# Cab_Board.net
KiCad netlist of a schematic drawn in EAGLE
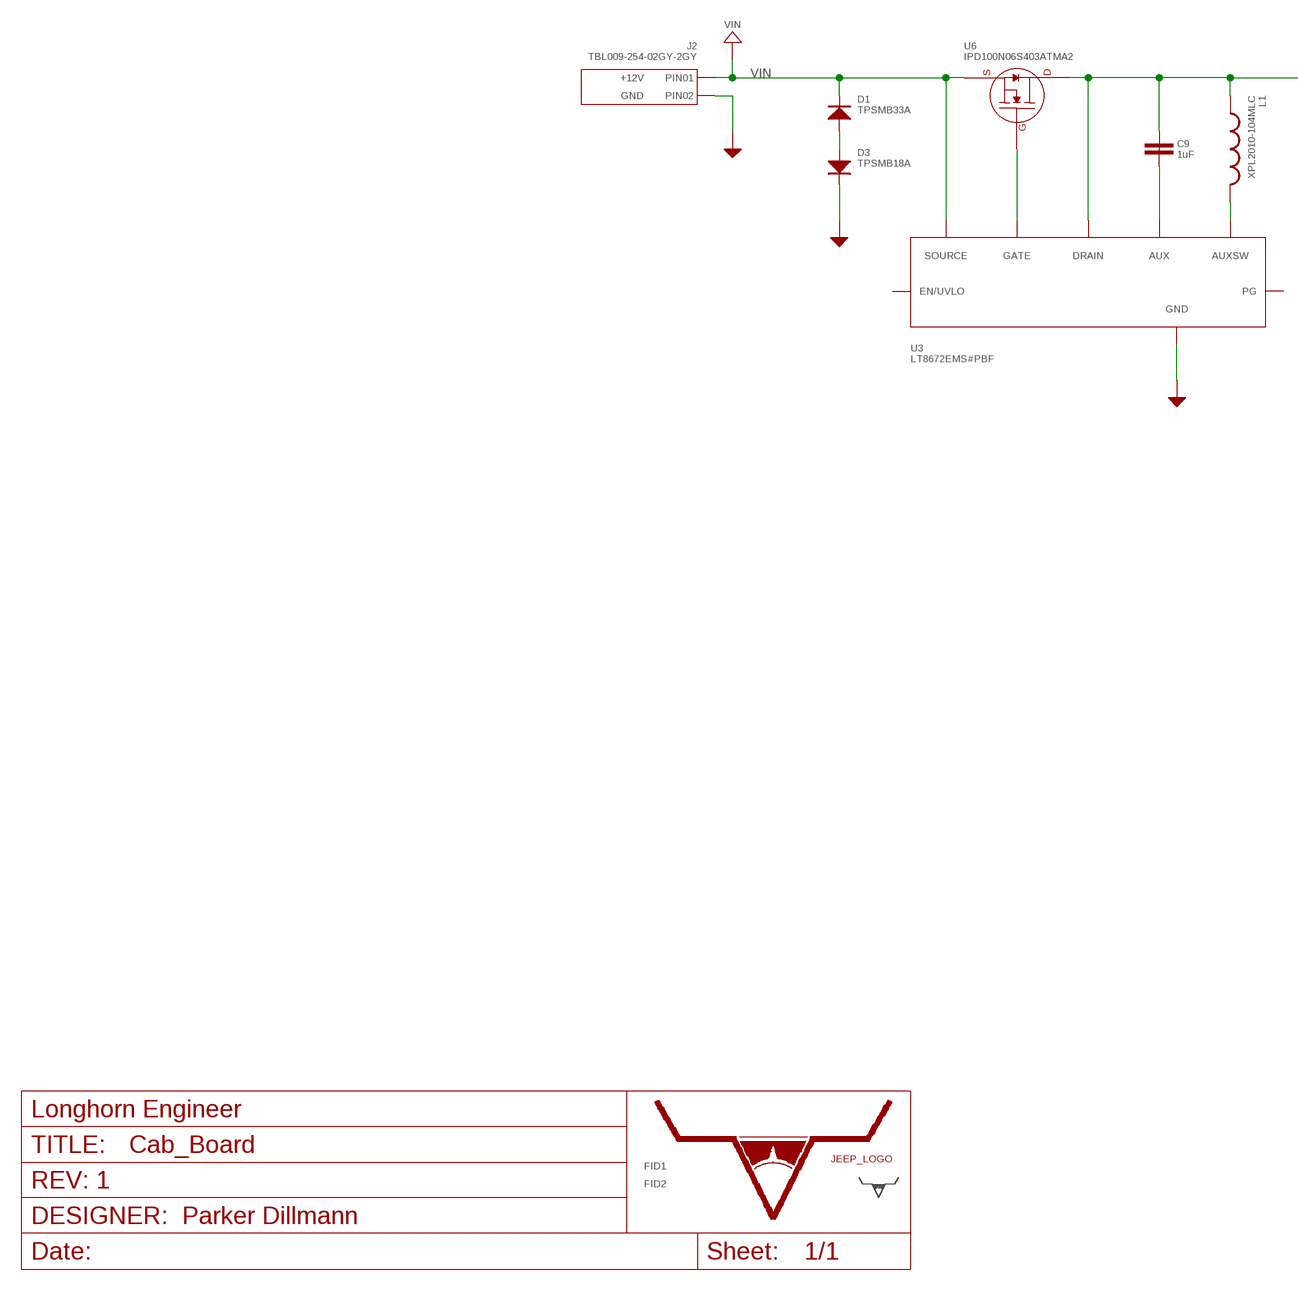
[diagram p0: schematic, sheet 1, part 1 of 3]
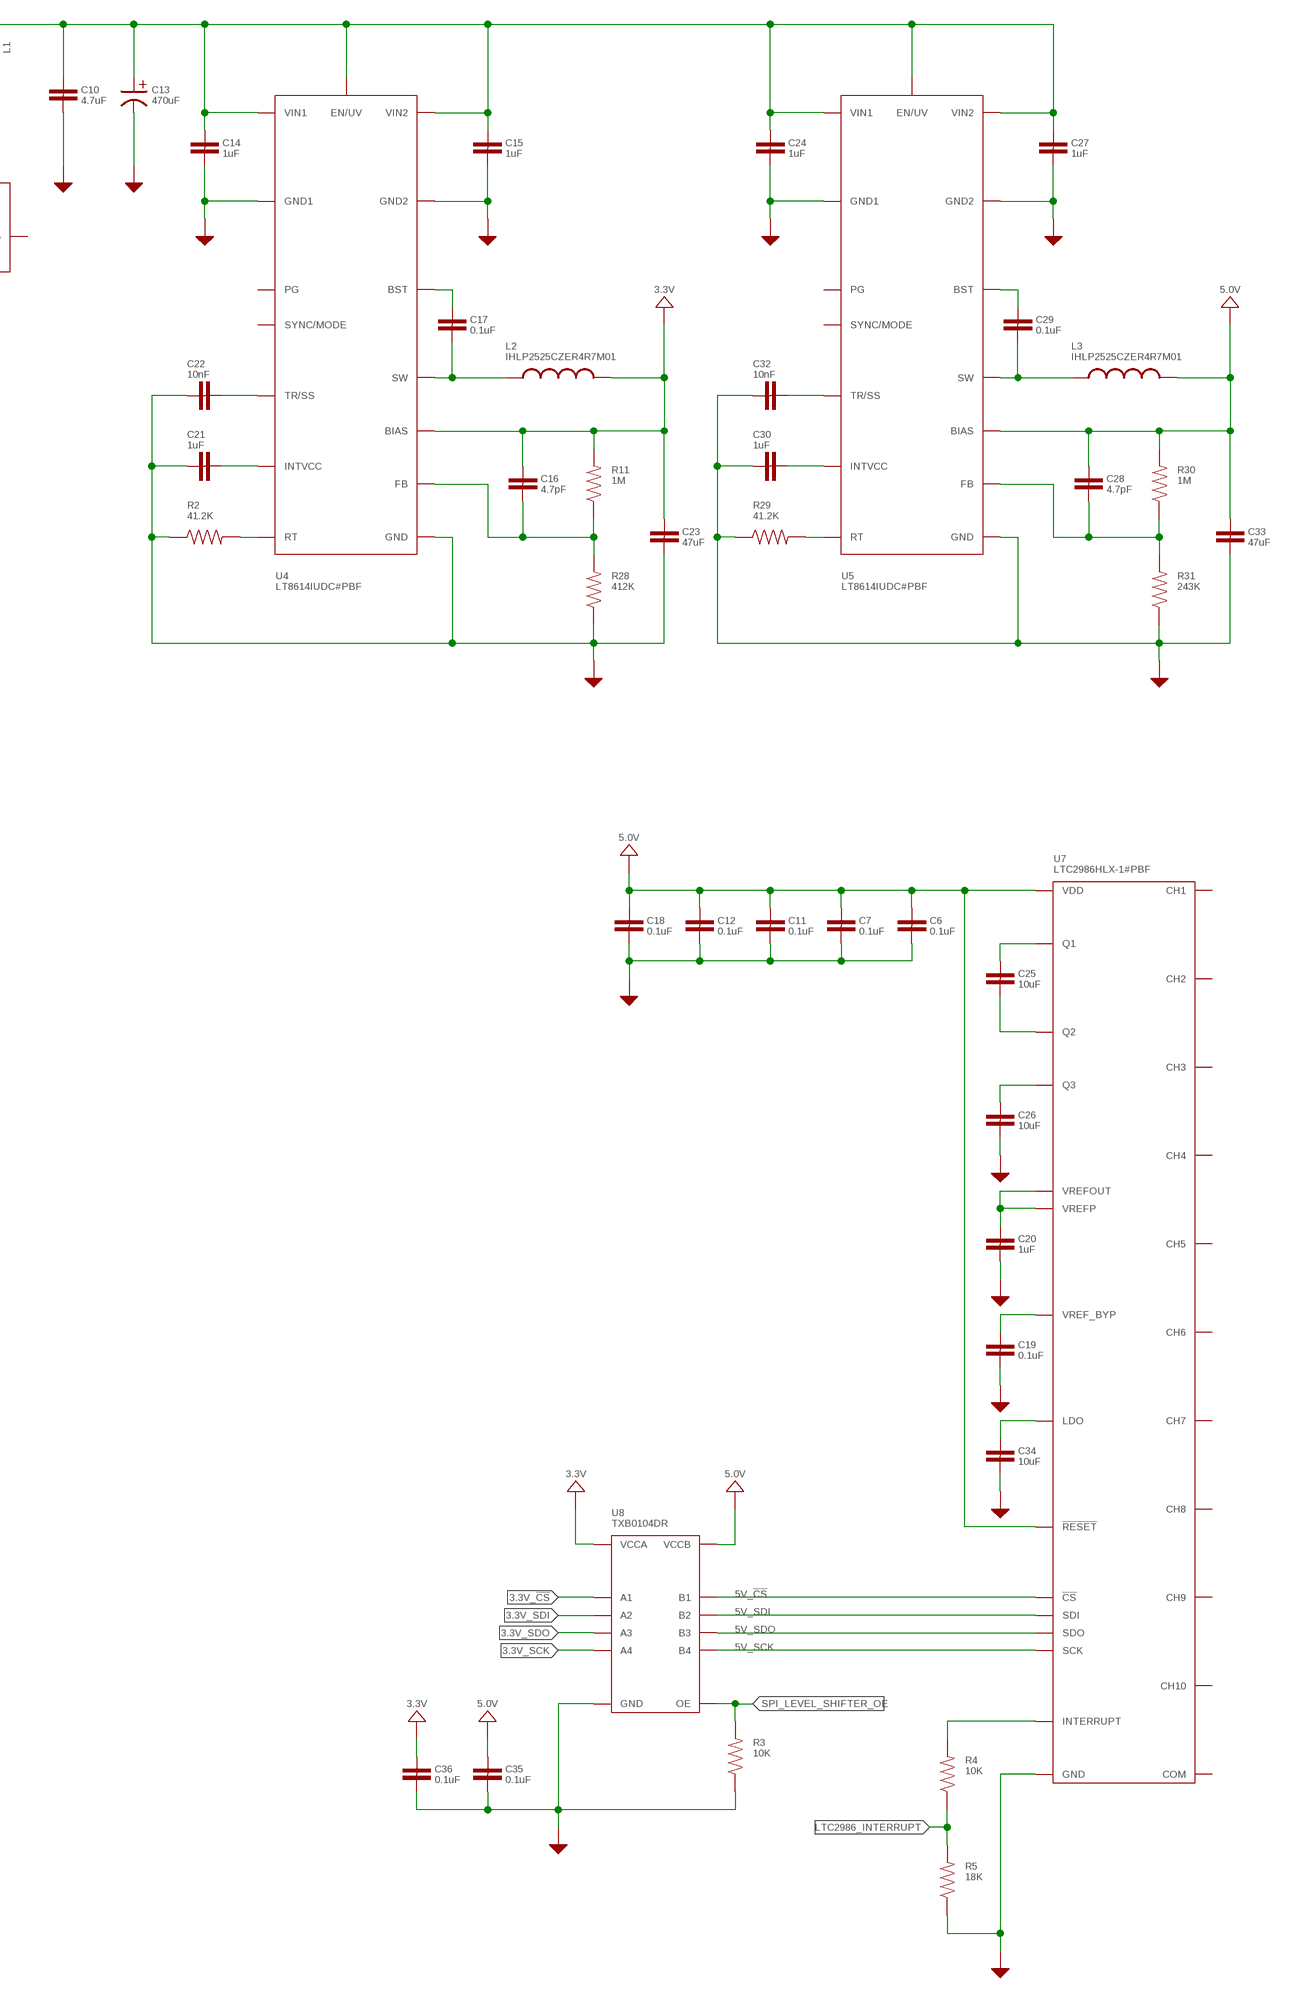
[diagram p1: schematic, sheet 1, part 2 of 3]
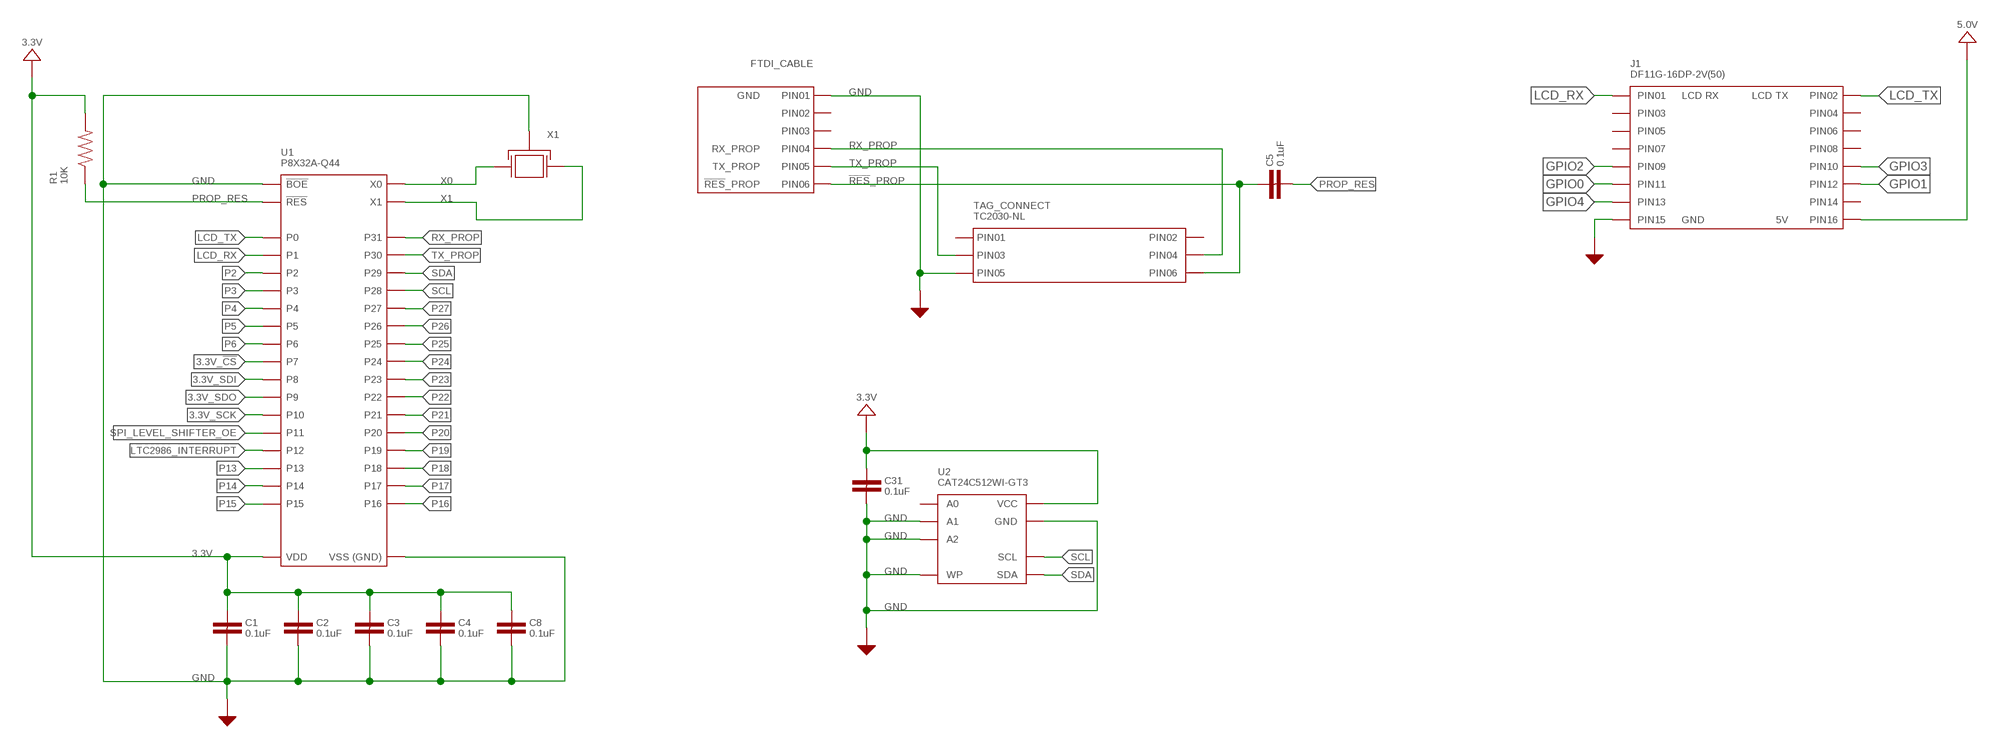
[diagram p2: schematic, sheet 1, part 3 of 3]

(export (version "E")
  (design (tool "Eeschema 10.0.6"))
  (components
    (comp (ref "C1")
      (value "0.1uF")
      (footprint "eagle-import:0805")
      (fields (field (name "MPN") "MF-CAP-0805-0.1uF"))
      (libsource (lib "eagle-import") (part "CAPACITOR_NON_POLAR_0805"))
    )
    (comp (ref "C2")
      (value "0.1uF")
      (footprint "eagle-import:0805")
      (fields (field (name "MPN") "MF-CAP-0805-0.1uF"))
      (libsource (lib "eagle-import") (part "CAPACITOR_NON_POLAR_0805"))
    )
    (comp (ref "C3")
      (value "0.1uF")
      (footprint "eagle-import:0805")
      (fields (field (name "MPN") "MF-CAP-0805-0.1uF"))
      (libsource (lib "eagle-import") (part "CAPACITOR_NON_POLAR_0805"))
    )
    (comp (ref "C4")
      (value "0.1uF")
      (footprint "eagle-import:0805")
      (fields (field (name "MPN") "MF-CAP-0805-0.1uF"))
      (libsource (lib "eagle-import") (part "CAPACITOR_NON_POLAR_0805"))
    )
    (comp (ref "C5")
      (value "0.1uF")
      (footprint "eagle-import:0603")
      (fields (field (name "MPN") "MF-CAP-0805-0.1uF"))
      (libsource (lib "eagle-import") (part "CAPACITOR_NON_POLAR_0603"))
    )
    (comp (ref "C6")
      (value "0.1uF")
      (footprint "eagle-import:0805")
      (fields (field (name "MPN") "MF-CAP-0805-0.1uF"))
      (libsource (lib "eagle-import") (part "CAPACITOR_NON_POLAR_0805"))
    )
    (comp (ref "C7")
      (value "0.1uF")
      (footprint "eagle-import:0805")
      (fields (field (name "MPN") "MF-CAP-0805-0.1uF"))
      (libsource (lib "eagle-import") (part "CAPACITOR_NON_POLAR_0805"))
    )
    (comp (ref "C8")
      (value "0.1uF")
      (footprint "eagle-import:0805")
      (fields (field (name "MPN") "MF-CAP-0805-0.1uF"))
      (libsource (lib "eagle-import") (part "CAPACITOR_NON_POLAR_0805"))
    )
    (comp (ref "C9")
      (value "1uF")
      (footprint "eagle-import:0805")
      (fields (field (name "MPN") "C0805X105K5RACAUTO"))
      (libsource (lib "eagle-import") (part "CAPACITOR_NON_POLAR_0805"))
    )
    (comp (ref "C10")
      (value "4.7uF")
      (footprint "eagle-import:1210")
      (fields (field (name "MPN") "UMJ325AB7475KMHP"))
      (libsource (lib "eagle-import") (part "CAPACITOR_NON_POLAR_1210"))
    )
    (comp (ref "C11")
      (value "0.1uF")
      (footprint "eagle-import:0805")
      (fields (field (name "MPN") "MF-CAP-0805-0.1uF"))
      (libsource (lib "eagle-import") (part "CAPACITOR_NON_POLAR_0805"))
    )
    (comp (ref "C12")
      (value "0.1uF")
      (footprint "eagle-import:0805")
      (fields (field (name "MPN") "MF-CAP-0805-0.1uF"))
      (libsource (lib "eagle-import") (part "CAPACITOR_NON_POLAR_0805"))
    )
    (comp (ref "C13")
      (value "470uF")
      (footprint "eagle-import:10MM_CAP_SMD")
      (fields (field (name "MPN") "EEH-ZS1V471P"))
      (libsource (lib "eagle-import") (part "CAPACITOR_POLARIZED_10MM_SMD"))
    )
    (comp (ref "C14")
      (value "1uF")
      (footprint "eagle-import:0805")
      (fields (field (name "MPN") "C0805X105K5RACAUTO"))
      (libsource (lib "eagle-import") (part "CAPACITOR_NON_POLAR_0805"))
    )
    (comp (ref "C15")
      (value "1uF")
      (footprint "eagle-import:0805")
      (fields (field (name "MPN") "C0805X105K5RACAUTO"))
      (libsource (lib "eagle-import") (part "CAPACITOR_NON_POLAR_0805"))
    )
    (comp (ref "C16")
      (value "4.7pF")
      (footprint "eagle-import:0603")
      (fields (field (name "MPN") "C0603C479D5HACTU"))
      (libsource (lib "eagle-import") (part "CAPACITOR_NON_POLAR_0603"))
    )
    (comp (ref "C17")
      (value "0.1uF")
      (footprint "eagle-import:0603")
      (fields (field (name "MPN") "MF-CAP-0603-0.1uF"))
      (libsource (lib "eagle-import") (part "CAPACITOR_NON_POLAR_0603"))
    )
    (comp (ref "C18")
      (value "0.1uF")
      (footprint "eagle-import:0805")
      (fields (field (name "MPN") "MF-CAP-0805-0.1uF"))
      (libsource (lib "eagle-import") (part "CAPACITOR_NON_POLAR_0805"))
    )
    (comp (ref "C19")
      (value "0.1uF")
      (footprint "eagle-import:0805")
      (fields (field (name "MPN") "MF-CAP-0805-0.1uF"))
      (libsource (lib "eagle-import") (part "CAPACITOR_NON_POLAR_0805"))
    )
    (comp (ref "C20")
      (value "1uF")
      (footprint "eagle-import:0805")
      (fields (field (name "MPN") "MF-CAP-0805-1uF"))
      (libsource (lib "eagle-import") (part "CAPACITOR_NON_POLAR_0805"))
    )
    (comp (ref "C21")
      (value "1uF")
      (footprint "eagle-import:0805")
      (fields (field (name "MPN") "C0805X105K5RACAUTO"))
      (libsource (lib "eagle-import") (part "CAPACITOR_NON_POLAR_0805"))
    )
    (comp (ref "C22")
      (value "10nF")
      (footprint "eagle-import:0603")
      (fields (field (name "MPN") "C0603X103K5RAC3316"))
      (libsource (lib "eagle-import") (part "CAPACITOR_NON_POLAR_0603"))
    )
    (comp (ref "C23")
      (value "47uF")
      (footprint "eagle-import:1210")
      (fields (field (name "MPN") "GCJ32ER70J476KE01L"))
      (libsource (lib "eagle-import") (part "CAPACITOR_NON_POLAR_1210"))
    )
    (comp (ref "C24")
      (value "1uF")
      (footprint "eagle-import:0805")
      (fields (field (name "MPN") "C0805X105K5RACAUTO"))
      (libsource (lib "eagle-import") (part "CAPACITOR_NON_POLAR_0805"))
    )
    (comp (ref "C25")
      (value "10uF")
      (footprint "eagle-import:1210")
      (fields (field (name "MPN") "CGA6P1X7R1N106K250AC"))
      (libsource (lib "eagle-import") (part "CAPACITOR_NON_POLAR_1210"))
    )
    (comp (ref "C26")
      (value "10uF")
      (footprint "eagle-import:1210")
      (fields (field (name "MPN") "CGA6P1X7R1N106K250AC"))
      (libsource (lib "eagle-import") (part "CAPACITOR_NON_POLAR_1210"))
    )
    (comp (ref "C27")
      (value "1uF")
      (footprint "eagle-import:0805")
      (fields (field (name "MPN") "C0805X105K5RACAUTO"))
      (libsource (lib "eagle-import") (part "CAPACITOR_NON_POLAR_0805"))
    )
    (comp (ref "C28")
      (value "4.7pF")
      (footprint "eagle-import:0603")
      (fields (field (name "MPN") "C0603C479D5HACTU"))
      (libsource (lib "eagle-import") (part "CAPACITOR_NON_POLAR_0603"))
    )
    (comp (ref "C29")
      (value "0.1uF")
      (footprint "eagle-import:0603")
      (fields (field (name "MPN") "MF-CAP-0603-0.1uF"))
      (libsource (lib "eagle-import") (part "CAPACITOR_NON_POLAR_0603"))
    )
    (comp (ref "C30")
      (value "1uF")
      (footprint "eagle-import:0805")
      (fields (field (name "MPN") "C0805X105K5RACAUTO"))
      (libsource (lib "eagle-import") (part "CAPACITOR_NON_POLAR_0805"))
    )
    (comp (ref "C31")
      (value "0.1uF")
      (footprint "eagle-import:0805")
      (fields (field (name "MPN") "MF-CAP-0805-0.1uF") (field (name "SPICEPREFIX") "C"))
      (libsource (lib "eagle-import") (part "CAPACITOR_NON_POLAR_0805"))
    )
    (comp (ref "C32")
      (value "10nF")
      (footprint "eagle-import:0603")
      (fields (field (name "MPN") "C0603X103K5RAC3316"))
      (libsource (lib "eagle-import") (part "CAPACITOR_NON_POLAR_0603"))
    )
    (comp (ref "C33")
      (value "47uF")
      (footprint "eagle-import:1210")
      (fields (field (name "MPN") "GCJ32ER70J476KE01L"))
      (libsource (lib "eagle-import") (part "CAPACITOR_NON_POLAR_1210"))
    )
    (comp (ref "C34")
      (value "10uF")
      (footprint "eagle-import:1210")
      (fields (field (name "MPN") "CGA6P1X7R1N106K250AC"))
      (libsource (lib "eagle-import") (part "CAPACITOR_NON_POLAR_1210"))
    )
    (comp (ref "C35")
      (value "0.1uF")
      (footprint "eagle-import:0805")
      (fields (field (name "MPN") "MF-CAP-0805-0.1uF"))
      (libsource (lib "eagle-import") (part "CAPACITOR_NON_POLAR_0805"))
    )
    (comp (ref "C36")
      (value "0.1uF")
      (footprint "eagle-import:0805")
      (fields (field (name "MPN") "MF-CAP-0805-0.1uF"))
      (libsource (lib "eagle-import") (part "CAPACITOR_NON_POLAR_0805"))
    )
    (comp (ref "D1")
      (value "TPSMB33A")
      (footprint "eagle-import:DO-214AA")
      (libsource (lib "eagle-import") (part "DIODE_DO-214AA"))
    )
    (comp (ref "D3")
      (value "TPSMB18A")
      (footprint "eagle-import:DO-214AA")
      (libsource (lib "eagle-import") (part "DIODE_DO-214AA"))
    )
    (comp (ref "FID1")
      (value "FIDUCIAL_0.5MM")
      (footprint "eagle-import:FIDUCIAL_0.5MM")
      (fields (field (name "HOUSEPART") "NO"))
      (libsource (lib "eagle-import") (part "FIDUCIAL_0.5MM"))
    )
    (comp (ref "FID2")
      (value "FIDUCIAL_0.5MM")
      (footprint "eagle-import:FIDUCIAL_0.5MM")
      (fields (field (name "HOUSEPART") "NO"))
      (libsource (lib "eagle-import") (part "FIDUCIAL_0.5MM"))
    )
    (comp (ref "FTDI_CABLE")
      (value "CON_01X06_2.54MM_PIN_HEADER")
      (footprint "eagle-import:2.54MM_01X06_PIN_HEADER")
      (fields
        (field (name "LABEL01") "GND")
        (field (name "LABEL04") "RX_PROP")
        (field (name "LABEL05") "TX_PROP")
        (field (name "LABEL06") "!RES!_PROP")
      )
      (libsource (lib "eagle-import") (part "CON_01X06_2.54MM_PIN_HEADER"))
    )
    (comp (ref "J1")
      (value "DF11G-16DP-2V(50)")
      (footprint "eagle-import:DF11G-16DP-2V(50)")
      (fields
        (field (name "LABEL01") "LCD RX")
        (field (name "LABEL02") "LCD TX")
        (field (name "LABEL15") "GND")
        (field (name "LABEL16") "5V")
      )
      (libsource (lib "eagle-import") (part "CON_02X08_DF11G-16DP-2V(50)"))
    )
    (comp (ref "J2")
      (value "TBL009-254-02GY-2GY")
      (footprint "eagle-import:TBL009-254-02GY-2GY")
      (fields (field (name "LABEL01") "+12V") (field (name "LABEL02") "GND"))
      (libsource (lib "eagle-import") (part "CON_01X02_TBL009-254-02GY-2GY"))
    )
    (comp (ref "L1")
      (value "XPL2010-104MLC")
      (footprint "eagle-import:XPL2010")
      (libsource (lib "eagle-import") (part "INDUCTOR_XPL2010"))
    )
    (comp (ref "L2")
      (value "IHLP2525CZER4R7M01")
      (footprint "eagle-import:IHLP-2525")
      (libsource (lib "eagle-import") (part "INDUCTOR_IHLP-2525"))
    )
    (comp (ref "L3")
      (value "IHLP2525CZER4R7M01")
      (footprint "eagle-import:IHLP-2525")
      (libsource (lib "eagle-import") (part "INDUCTOR_IHLP-2525"))
    )
    (comp (ref "R1")
      (value "10K")
      (footprint "eagle-import:0805")
      (libsource (lib "eagle-import") (part "RESISTOR_0805"))
    )
    (comp (ref "R2")
      (value "41.2K")
      (footprint "eagle-import:0603")
      (libsource (lib "eagle-import") (part "RESISTOR_0603"))
    )
    (comp (ref "R3")
      (value "10K")
      (footprint "eagle-import:0603")
      (fields (field (name "MPN") "MF-RES-0603-10K"))
      (libsource (lib "eagle-import") (part "RESISTOR_0603"))
    )
    (comp (ref "R4")
      (value "10K")
      (footprint "eagle-import:0603")
      (fields (field (name "MPN") "MF-RES-0603-10K"))
      (libsource (lib "eagle-import") (part "RESISTOR_0603"))
    )
    (comp (ref "R5")
      (value "18K")
      (footprint "eagle-import:0603")
      (libsource (lib "eagle-import") (part "RESISTOR_0603"))
    )
    (comp (ref "R11")
      (value "1M")
      (footprint "eagle-import:0603")
      (libsource (lib "eagle-import") (part "RESISTOR_0603"))
    )
    (comp (ref "R28")
      (value "412K")
      (footprint "eagle-import:0603")
      (libsource (lib "eagle-import") (part "RESISTOR_0603"))
    )
    (comp (ref "R29")
      (value "41.2K")
      (footprint "eagle-import:0603")
      (libsource (lib "eagle-import") (part "RESISTOR_0603"))
    )
    (comp (ref "R30")
      (value "1M")
      (footprint "eagle-import:0603")
      (libsource (lib "eagle-import") (part "RESISTOR_0603"))
    )
    (comp (ref "R31")
      (value "243K")
      (footprint "eagle-import:0603")
      (libsource (lib "eagle-import") (part "RESISTOR_0603"))
    )
    (comp (ref "TAG_CONNECT")
      (value "TC2030-NL")
      (footprint "eagle-import:TC2030")
      (libsource (lib "eagle-import") (part "CON_02X03_TC2030"))
    )
    (comp (ref "U$1")
      (value "LHE_FRAME")
      (footprint "eagle-import:LHE_FRAME")
      (fields (field (name "DNAME") "Parker Dillmann") (field (name "REVNUM") "REV: 1"))
      (libsource (lib "eagle-import") (part "LHE_FRAME"))
    )
    (comp (ref "U$35")
      (value "JEEP_LOGO_SILK_MEDIUM")
      (footprint "eagle-import:JEEP_SILK_MEDIUM")
      (libsource (lib "eagle-import") (part "JEEP_LOGO_SILK_MEDIUM"))
    )
    (comp (ref "U$42")
      (value "LHE_LOGOLHE_LOGO")
      (footprint "eagle-import:LHE_LOGO")
      (libsource (lib "eagle-import") (part "LHE_LOGOLHE_LOGO"))
    )
    (comp (ref "U1")
      (value "P8X32A-Q44")
      (footprint "eagle-import:LQFP44")
      (fields (field (name "HOUSEPART") "NO"))
      (libsource (lib "eagle-import") (part "P8X32A-Q44"))
    )
    (comp (ref "U2")
      (value "CAT24C512WI-GT3")
      (footprint "eagle-import:SOIC-8_W")
      (fields (field (name "SPICEPREFIX") "X"))
      (libsource (lib "eagle-import") (part "EEPROM_I2CSOIC-8_W"))
    )
    (comp (ref "U3")
      (value "LT8672EMS#PBF")
      (footprint "eagle-import:LT8672_MSOP-10")
      (libsource (lib "eagle-import") (part "LT8672EMS#PBF"))
    )
    (comp (ref "U4")
      (value "LT8614IUDC#PBF")
      (footprint "eagle-import:LT8614_QFN-18")
      (libsource (lib "eagle-import") (part "LT8614IUDC#PBF"))
    )
    (comp (ref "U5")
      (value "LT8614IUDC#PBF")
      (footprint "eagle-import:LT8614_QFN-18")
      (libsource (lib "eagle-import") (part "LT8614IUDC#PBF"))
    )
    (comp (ref "U6")
      (value "IPD100N06S403ATMA2")
      (footprint "eagle-import:TO-252-3")
      (libsource (lib "eagle-import") (part "MOSFET_N-CHANNEL_SINGLE_TO-252-3"))
    )
    (comp (ref "U7")
      (value "LTC2986HLX-1#PBF")
      (footprint "eagle-import:LQFP-48")
      (fields (field (name "MPN") "LTC2986HLX#PBF") (field (name "MPN_1") "LTC2986HLX-1#PBF"))
      (libsource (lib "eagle-import") (part "LTC2986HLX#PBF"))
    )
    (comp (ref "U8")
      (value "TXB0104DR")
      (footprint "eagle-import:TXB0104_SOIC-14")
      (fields (field (name "MPN") "TXB0104DR "))
      (libsource (lib "eagle-import") (part "TXB0104DR"))
    )
    (comp (ref "X1")
      (value "6.0MHz")
      (footprint "eagle-import:7MMX5MM")
      (fields (field (name "HOUSEPART") "NO") (field (name "MPN") "ABMM-6.000MHZ-B2-T"))
      (libsource (lib "eagle-import") (part "CYRSTAL_GND_ABMM"))
    )
  )
  (nets
    (net (code "1") (name "/3.3V_~{CS}") (class "Default")
      (node (ref "U1") (pin "4") (pinfunction "P7_4") (pintype "bidirectional"))
      (node (ref "U8") (pin "2") (pinfunction "A1_2") (pintype "bidirectional"))
    )
    (net (code "2") (name "/5V_SCK") (class "Default")
      (node (ref "U7") (pin "P$38") (pinfunction "SCK_P$38") (pintype "bidirectional"))
      (node (ref "U8") (pin "10") (pinfunction "B4_10") (pintype "bidirectional"))
    )
    (net (code "3") (name "/5V_SDI") (class "Default")
      (node (ref "U7") (pin "P$40") (pinfunction "SDI_P$40") (pintype "bidirectional"))
      (node (ref "U8") (pin "12") (pinfunction "B2_12") (pintype "bidirectional"))
    )
    (net (code "4") (name "/5V_SDO") (class "Default")
      (node (ref "U7") (pin "P$39") (pinfunction "SDO_P$39") (pintype "bidirectional"))
      (node (ref "U8") (pin "11") (pinfunction "B3_11") (pintype "bidirectional"))
    )
    (net (code "5") (name "/5V_~{CS}") (class "Default")
      (node (ref "U7") (pin "P$41") (pinfunction "~{CS}_P$41") (pintype "bidirectional"))
      (node (ref "U8") (pin "13") (pinfunction "B1_13") (pintype "bidirectional"))
    )
    (net (code "6") (name "/X0") (class "Default")
      (node (ref "U1") (pin "29") (pinfunction "X0_29") (pintype "bidirectional"))
      (node (ref "X1") (pin "P$3") (pinfunction "X1_P$3") (pintype "bidirectional"))
    )
    (net (code "7") (name "/X1") (class "Default")
      (node (ref "U1") (pin "28") (pinfunction "X1_28") (pintype "bidirectional"))
      (node (ref "X1") (pin "P$1") (pinfunction "X0_P$1") (pintype "bidirectional"))
    )
    (net (code "8") (name "/~{RES}_PROP") (class "Default")
      (node (ref "C5") (pin "1") (pinfunction "1_1") (pintype "passive"))
      (node (ref "FTDI_CABLE") (pin "6") (pinfunction "6_6") (pintype "passive"))
      (node (ref "TAG_CONNECT") (pin "P$6") (pinfunction "PIN6_P$6") (pintype "bidirectional"))
    )
    (net (code "9") (name "3.3V") (class "Default")
      (node (ref "C1") (pin "1") (pinfunction "1_1") (pintype "passive"))
      (node (ref "C16") (pin "1") (pinfunction "1_1") (pintype "passive"))
      (node (ref "C2") (pin "1") (pinfunction "1_1") (pintype "passive"))
      (node (ref "C23") (pin "1") (pinfunction "1_1") (pintype "passive"))
      (node (ref "C3") (pin "1") (pinfunction "1_1") (pintype "passive"))
      (node (ref "C31") (pin "1") (pinfunction "1_1") (pintype "passive"))
      (node (ref "C36") (pin "1") (pinfunction "1_1") (pintype "passive"))
      (node (ref "C4") (pin "1") (pinfunction "1_1") (pintype "passive"))
      (node (ref "C8") (pin "1") (pinfunction "1_1") (pintype "passive"))
      (node (ref "L2") (pin "P$2") (pinfunction "P$2_P$2") (pintype "bidirectional"))
      (node (ref "R1") (pin "2") (pinfunction "2_2") (pintype "passive"))
      (node (ref "R11") (pin "2") (pinfunction "2_2") (pintype "passive"))
      (node (ref "U1") (pin "18") (pinfunction "VDD_18") (pintype "power_in"))
      (node (ref "U1") (pin "30") (pinfunction "VDD_30") (pintype "power_in"))
      (node (ref "U1") (pin "40") (pinfunction "VDD_40") (pintype "power_in"))
      (node (ref "U1") (pin "8") (pinfunction "VDD_8") (pintype "power_in"))
      (node (ref "U2") (pin "8") (pinfunction "VCC_8") (pintype "bidirectional"))
      (node (ref "U4") (pin "1") (pinfunction "BIAS_1") (pintype "bidirectional"))
      (node (ref "U8") (pin "1") (pinfunction "VCCA_1") (pintype "bidirectional"))
    )
    (net (code "10") (name "3.3V_SCK") (class "Default")
      (node (ref "U1") (pin "11") (pinfunction "P10_11") (pintype "bidirectional"))
      (node (ref "U8") (pin "5") (pinfunction "A4_5") (pintype "bidirectional"))
    )
    (net (code "11") (name "3.3V_SDI") (class "Default")
      (node (ref "U1") (pin "9") (pinfunction "P8_9") (pintype "bidirectional"))
      (node (ref "U8") (pin "3") (pinfunction "A2_3") (pintype "bidirectional"))
    )
    (net (code "12") (name "3.3V_SDO") (class "Default")
      (node (ref "U1") (pin "10") (pinfunction "P9_10") (pintype "bidirectional"))
      (node (ref "U8") (pin "4") (pinfunction "A3_4") (pintype "bidirectional"))
    )
    (net (code "13") (name "5.0V") (class "Default")
      (node (ref "C11") (pin "1") (pinfunction "1_1") (pintype "passive"))
      (node (ref "C12") (pin "1") (pinfunction "1_1") (pintype "passive"))
      (node (ref "C18") (pin "1") (pinfunction "1_1") (pintype "passive"))
      (node (ref "C28") (pin "1") (pinfunction "1_1") (pintype "passive"))
      (node (ref "C33") (pin "1") (pinfunction "1_1") (pintype "passive"))
      (node (ref "C35") (pin "1") (pinfunction "1_1") (pintype "passive"))
      (node (ref "C6") (pin "1") (pinfunction "1_1") (pintype "passive"))
      (node (ref "C7") (pin "1") (pinfunction "1_1") (pintype "passive"))
      (node (ref "J1") (pin "P$16") (pinfunction "16_P$16") (pintype "bidirectional"))
      (node (ref "L3") (pin "P$2") (pinfunction "P$2_P$2") (pintype "bidirectional"))
      (node (ref "R30") (pin "2") (pinfunction "2_2") (pintype "passive"))
      (node (ref "U5") (pin "1") (pinfunction "BIAS_1") (pintype "bidirectional"))
      (node (ref "U7") (pin "P$2") (pinfunction "VDD_P$2") (pintype "bidirectional"))
      (node (ref "U7") (pin "P$4") (pinfunction "VDD_P$4") (pintype "bidirectional"))
      (node (ref "U7") (pin "P$42") (pinfunction "~{RESET}_P$42") (pintype "bidirectional"))
      (node (ref "U7") (pin "P$45") (pinfunction "VDD_P$45") (pintype "bidirectional"))
      (node (ref "U7") (pin "P$6") (pinfunction "VDD_P$6") (pintype "bidirectional"))
      (node (ref "U7") (pin "P$8") (pinfunction "VDD_P$8") (pintype "bidirectional"))
      (node (ref "U8") (pin "14") (pinfunction "VCCB_14") (pintype "bidirectional"))
    )
    (net (code "14") (name "GND_RAIL") (class "Default")
      (node (ref "C1") (pin "2") (pinfunction "2_2") (pintype "passive"))
      (node (ref "C10") (pin "2") (pinfunction "2_2") (pintype "passive"))
      (node (ref "C11") (pin "2") (pinfunction "2_2") (pintype "passive"))
      (node (ref "C12") (pin "2") (pinfunction "2_2") (pintype "passive"))
      (node (ref "C13") (pin "NEG") (pinfunction "NEG_NEG") (pintype "bidirectional"))
      (node (ref "C14") (pin "2") (pinfunction "2_2") (pintype "passive"))
      (node (ref "C15") (pin "2") (pinfunction "2_2") (pintype "passive"))
      (node (ref "C18") (pin "2") (pinfunction "2_2") (pintype "passive"))
      (node (ref "C19") (pin "2") (pinfunction "2_2") (pintype "passive"))
      (node (ref "C2") (pin "2") (pinfunction "2_2") (pintype "passive"))
      (node (ref "C20") (pin "2") (pinfunction "2_2") (pintype "passive"))
      (node (ref "C21") (pin "1") (pinfunction "1_1") (pintype "passive"))
      (node (ref "C22") (pin "1") (pinfunction "1_1") (pintype "passive"))
      (node (ref "C23") (pin "2") (pinfunction "2_2") (pintype "passive"))
      (node (ref "C24") (pin "2") (pinfunction "2_2") (pintype "passive"))
      (node (ref "C26") (pin "2") (pinfunction "2_2") (pintype "passive"))
      (node (ref "C27") (pin "2") (pinfunction "2_2") (pintype "passive"))
      (node (ref "C3") (pin "2") (pinfunction "2_2") (pintype "passive"))
      (node (ref "C30") (pin "1") (pinfunction "1_1") (pintype "passive"))
      (node (ref "C31") (pin "2") (pinfunction "2_2") (pintype "passive"))
      (node (ref "C32") (pin "1") (pinfunction "1_1") (pintype "passive"))
      (node (ref "C33") (pin "2") (pinfunction "2_2") (pintype "passive"))
      (node (ref "C34") (pin "2") (pinfunction "2_2") (pintype "passive"))
      (node (ref "C35") (pin "2") (pinfunction "2_2") (pintype "passive"))
      (node (ref "C36") (pin "2") (pinfunction "2_2") (pintype "passive"))
      (node (ref "C4") (pin "2") (pinfunction "2_2") (pintype "passive"))
      (node (ref "C6") (pin "2") (pinfunction "2_2") (pintype "passive"))
      (node (ref "C7") (pin "2") (pinfunction "2_2") (pintype "passive"))
      (node (ref "C8") (pin "2") (pinfunction "2_2") (pintype "passive"))
      (node (ref "D3") (pin "C") (pinfunction "CATHODE_C") (pintype "bidirectional"))
      (node (ref "FTDI_CABLE") (pin "1") (pinfunction "1_1") (pintype "passive"))
      (node (ref "J1") (pin "P$15") (pinfunction "15_P$15") (pintype "bidirectional"))
      (node (ref "J2") (pin "2A") (pinfunction "PIN2_2A") (pintype "bidirectional"))
      (node (ref "J2") (pin "2B") (pinfunction "PIN2_2B") (pintype "bidirectional"))
      (node (ref "R2") (pin "1") (pinfunction "1_1") (pintype "passive"))
      (node (ref "R28") (pin "1") (pinfunction "1_1") (pintype "passive"))
      (node (ref "R29") (pin "1") (pinfunction "1_1") (pintype "passive"))
      (node (ref "R3") (pin "1") (pinfunction "1_1") (pintype "passive"))
      (node (ref "R31") (pin "1") (pinfunction "1_1") (pintype "passive"))
      (node (ref "R5") (pin "1") (pinfunction "1_1") (pintype "passive"))
      (node (ref "TAG_CONNECT") (pin "P$5") (pinfunction "PIN5_P$5") (pintype "bidirectional"))
      (node (ref "U1") (pin "17") (pinfunction "VSS_17") (pintype "power_in"))
      (node (ref "U1") (pin "27") (pinfunction "VSS_27") (pintype "power_in"))
      (node (ref "U1") (pin "39") (pinfunction "VSS_39") (pintype "power_in"))
      (node (ref "U1") (pin "5") (pinfunction "VSS_5") (pintype "power_in"))
      (node (ref "U1") (pin "6") (pinfunction "BOE'_6") (pintype "bidirectional"))
      (node (ref "U2") (pin "2") (pinfunction "A1_2") (pintype "bidirectional"))
      (node (ref "U2") (pin "3") (pinfunction "A2_3") (pintype "bidirectional"))
      (node (ref "U2") (pin "4") (pinfunction "GND_4") (pintype "bidirectional"))
      (node (ref "U2") (pin "7") (pinfunction "WP_7") (pintype "bidirectional"))
      (node (ref "U3") (pin "2") (pinfunction "GND_2") (pintype "bidirectional"))
      (node (ref "U3") (pin "4") (pinfunction "GND_4") (pintype "bidirectional"))
      (node (ref "U4") (pin "10") (pinfunction "GND2_10") (pintype "bidirectional"))
      (node (ref "U4") (pin "11") (pinfunction "GND2_11") (pintype "bidirectional"))
      (node (ref "U4") (pin "18") (pinfunction "GND_18") (pintype "bidirectional"))
      (node (ref "U4") (pin "6") (pinfunction "GND1_6") (pintype "bidirectional"))
      (node (ref "U4") (pin "7") (pinfunction "GND1_7") (pintype "bidirectional"))
      (node (ref "U5") (pin "10") (pinfunction "GND2_10") (pintype "bidirectional"))
      (node (ref "U5") (pin "11") (pinfunction "GND2_11") (pintype "bidirectional"))
      (node (ref "U5") (pin "18") (pinfunction "GND_18") (pintype "bidirectional"))
      (node (ref "U5") (pin "6") (pinfunction "GND1_6") (pintype "bidirectional"))
      (node (ref "U5") (pin "7") (pinfunction "GND1_7") (pintype "bidirectional"))
      (node (ref "U7") (pin "P$1") (pinfunction "GND_P$1") (pintype "bidirectional"))
      (node (ref "U7") (pin "P$12") (pinfunction "GND_P$12") (pintype "bidirectional"))
      (node (ref "U7") (pin "P$15") (pinfunction "GND_P$15") (pintype "bidirectional"))
      (node (ref "U7") (pin "P$26") (pinfunction "GND_P$26") (pintype "bidirectional"))
      (node (ref "U7") (pin "P$27") (pinfunction "GND_P$27") (pintype "bidirectional"))
      (node (ref "U7") (pin "P$28") (pinfunction "GND_P$28") (pintype "bidirectional"))
      (node (ref "U7") (pin "P$29") (pinfunction "GND_P$29") (pintype "bidirectional"))
      (node (ref "U7") (pin "P$3") (pinfunction "GND_P$3") (pintype "bidirectional"))
      (node (ref "U7") (pin "P$30") (pinfunction "GND_P$30") (pintype "bidirectional"))
      (node (ref "U7") (pin "P$31") (pinfunction "GND_P$31") (pintype "bidirectional"))
      (node (ref "U7") (pin "P$32") (pinfunction "GND_P$32") (pintype "bidirectional"))
      (node (ref "U7") (pin "P$33") (pinfunction "GND_P$33") (pintype "bidirectional"))
      (node (ref "U7") (pin "P$34") (pinfunction "GND_P$34") (pintype "bidirectional"))
      (node (ref "U7") (pin "P$35") (pinfunction "GND_P$35") (pintype "bidirectional"))
      (node (ref "U7") (pin "P$44") (pinfunction "GND_P$44") (pintype "bidirectional"))
      (node (ref "U7") (pin "P$5") (pinfunction "GND_P$5") (pintype "bidirectional"))
      (node (ref "U7") (pin "P$7") (pinfunction "GND_P$7") (pintype "bidirectional"))
      (node (ref "U7") (pin "P$9") (pinfunction "GND_P$9") (pintype "bidirectional"))
      (node (ref "U8") (pin "7") (pinfunction "GND_7") (pintype "bidirectional"))
      (node (ref "X1") (pin "P$2") (pinfunction "GND_P$2") (pintype "bidirectional"))
      (node (ref "X1") (pin "P$4") (pinfunction "GND_P$4") (pintype "bidirectional"))
    )
    (net (code "15") (name "GPIO0") (class "Default")
      (node (ref "J1") (pin "P$11") (pinfunction "11_P$11") (pintype "bidirectional"))
    )
    (net (code "16") (name "GPIO1") (class "Default")
      (node (ref "J1") (pin "P$12") (pinfunction "12_P$12") (pintype "bidirectional"))
    )
    (net (code "17") (name "GPIO2") (class "Default")
      (node (ref "J1") (pin "P$9") (pinfunction "9_P$9") (pintype "bidirectional"))
    )
    (net (code "18") (name "GPIO3") (class "Default")
      (node (ref "J1") (pin "P$10") (pinfunction "10_P$10") (pintype "bidirectional"))
    )
    (net (code "19") (name "GPIO4") (class "Default")
      (node (ref "J1") (pin "P$13") (pinfunction "13_P$13") (pintype "bidirectional"))
    )
    (net (code "20") (name "LCD_RX") (class "Default")
      (node (ref "J1") (pin "P$1") (pinfunction "1_P$1") (pintype "bidirectional"))
      (node (ref "U1") (pin "42") (pinfunction "P1_42") (pintype "bidirectional"))
    )
    (net (code "21") (name "LCD_TX") (class "Default")
      (node (ref "J1") (pin "P$2") (pinfunction "2_P$2") (pintype "bidirectional"))
      (node (ref "U1") (pin "41") (pinfunction "P0_41") (pintype "bidirectional"))
    )
    (net (code "22") (name "LTC2986_INTERRUPT") (class "Default")
      (node (ref "R4") (pin "1") (pinfunction "1_1") (pintype "passive"))
      (node (ref "R5") (pin "2") (pinfunction "2_2") (pintype "passive"))
      (node (ref "U1") (pin "13") (pinfunction "P12_13") (pintype "bidirectional"))
    )
    (net (code "23") (name "Net-(C17-Pad2)") (class "Default")
      (node (ref "C17") (pin "2") (pinfunction "2_2") (pintype "passive"))
      (node (ref "L2") (pin "P$1") (pinfunction "P$1_P$1") (pintype "bidirectional"))
      (node (ref "U4") (pin "21") (pinfunction "SW_21") (pintype "bidirectional"))
      (node (ref "U4") (pin "22") (pinfunction "SW_22") (pintype "bidirectional"))
      (node (ref "U4") (pin "8") (pinfunction "SW_8") (pintype "bidirectional"))
      (node (ref "U4") (pin "9") (pinfunction "SW_9") (pintype "bidirectional"))
    )
    (net (code "24") (name "Net-(C29-Pad2)") (class "Default")
      (node (ref "C29") (pin "2") (pinfunction "2_2") (pintype "passive"))
      (node (ref "L3") (pin "P$1") (pinfunction "P$1_P$1") (pintype "bidirectional"))
      (node (ref "U5") (pin "21") (pinfunction "SW_21") (pintype "bidirectional"))
      (node (ref "U5") (pin "22") (pinfunction "SW_22") (pintype "bidirectional"))
      (node (ref "U5") (pin "8") (pinfunction "SW_8") (pintype "bidirectional"))
      (node (ref "U5") (pin "9") (pinfunction "SW_9") (pintype "bidirectional"))
    )
    (net (code "25") (name "Net-(D1-ANODE)") (class "Default")
      (node (ref "D1") (pin "A") (pinfunction "ANODE_A") (pintype "bidirectional"))
      (node (ref "D3") (pin "A") (pinfunction "ANODE_A") (pintype "bidirectional"))
    )
    (net (code "26") (name "Net-(U3-AUX)") (class "Default")
      (node (ref "C9") (pin "2") (pinfunction "2_2") (pintype "passive"))
      (node (ref "U3") (pin "7") (pinfunction "AUX_7") (pintype "bidirectional"))
    )
    (net (code "27") (name "Net-(U3-AUXSW)") (class "Default")
      (node (ref "L1") (pin "P$2") (pinfunction "P$2_P$2") (pintype "bidirectional"))
      (node (ref "U3") (pin "6") (pinfunction "AUXSW_6") (pintype "bidirectional"))
    )
    (net (code "28") (name "Net-(U3-DRAIN)") (class "Default")
      (node (ref "C10") (pin "1") (pinfunction "1_1") (pintype "passive"))
      (node (ref "C13") (pin "POS") (pinfunction "POS_POS") (pintype "bidirectional"))
      (node (ref "C14") (pin "1") (pinfunction "1_1") (pintype "passive"))
      (node (ref "C15") (pin "1") (pinfunction "1_1") (pintype "passive"))
      (node (ref "C24") (pin "1") (pinfunction "1_1") (pintype "passive"))
      (node (ref "C27") (pin "1") (pinfunction "1_1") (pintype "passive"))
      (node (ref "C9") (pin "1") (pinfunction "1_1") (pintype "passive"))
      (node (ref "L1") (pin "P$1") (pinfunction "P$1_P$1") (pintype "bidirectional"))
      (node (ref "U3") (pin "8") (pinfunction "DRAIN_8") (pintype "bidirectional"))
      (node (ref "U4") (pin "13") (pinfunction "VIN2_13") (pintype "bidirectional"))
      (node (ref "U4") (pin "14") (pinfunction "EN/UV_14") (pintype "bidirectional"))
      (node (ref "U4") (pin "4") (pinfunction "VIN1_4") (pintype "bidirectional"))
      (node (ref "U5") (pin "13") (pinfunction "VIN2_13") (pintype "bidirectional"))
      (node (ref "U5") (pin "14") (pinfunction "EN/UV_14") (pintype "bidirectional"))
      (node (ref "U5") (pin "4") (pinfunction "VIN1_4") (pintype "bidirectional"))
      (node (ref "U6") (pin "PAD") (pinfunction "DRAIN_PAD") (pintype "bidirectional"))
    )
    (net (code "29") (name "Net-(U3-GATE)") (class "Default")
      (node (ref "U3") (pin "10") (pinfunction "GATE_10") (pintype "bidirectional"))
      (node (ref "U6") (pin "1") (pinfunction "GATE_1") (pintype "bidirectional"))
    )
    (net (code "30") (name "Net-(U4-BST)") (class "Default")
      (node (ref "C17") (pin "1") (pinfunction "1_1") (pintype "passive"))
      (node (ref "U4") (pin "3") (pinfunction "BST_3") (pintype "bidirectional"))
    )
    (net (code "31") (name "Net-(U4-FB)") (class "Default")
      (node (ref "C16") (pin "2") (pinfunction "2_2") (pintype "passive"))
      (node (ref "R11") (pin "1") (pinfunction "1_1") (pintype "passive"))
      (node (ref "R28") (pin "2") (pinfunction "2_2") (pintype "passive"))
      (node (ref "U4") (pin "20") (pinfunction "FB_20") (pintype "bidirectional"))
    )
    (net (code "32") (name "Net-(U4-INTVCC)") (class "Default")
      (node (ref "C21") (pin "2") (pinfunction "2_2") (pintype "passive"))
      (node (ref "U4") (pin "2") (pinfunction "INTVCC_2") (pintype "bidirectional"))
    )
    (net (code "33") (name "Net-(U4-RT)") (class "Default")
      (node (ref "R2") (pin "2") (pinfunction "2_2") (pintype "passive"))
      (node (ref "U4") (pin "15") (pinfunction "RT_15") (pintype "bidirectional"))
    )
    (net (code "34") (name "Net-(U4-TR{slash}SS)") (class "Default")
      (node (ref "C22") (pin "2") (pinfunction "2_2") (pintype "passive"))
      (node (ref "U4") (pin "16") (pinfunction "TR/SS_16") (pintype "bidirectional"))
    )
    (net (code "35") (name "Net-(U5-BST)") (class "Default")
      (node (ref "C29") (pin "1") (pinfunction "1_1") (pintype "passive"))
      (node (ref "U5") (pin "3") (pinfunction "BST_3") (pintype "bidirectional"))
    )
    (net (code "36") (name "Net-(U5-FB)") (class "Default")
      (node (ref "C28") (pin "2") (pinfunction "2_2") (pintype "passive"))
      (node (ref "R30") (pin "1") (pinfunction "1_1") (pintype "passive"))
      (node (ref "R31") (pin "2") (pinfunction "2_2") (pintype "passive"))
      (node (ref "U5") (pin "20") (pinfunction "FB_20") (pintype "bidirectional"))
    )
    (net (code "37") (name "Net-(U5-INTVCC)") (class "Default")
      (node (ref "C30") (pin "2") (pinfunction "2_2") (pintype "passive"))
      (node (ref "U5") (pin "2") (pinfunction "INTVCC_2") (pintype "bidirectional"))
    )
    (net (code "38") (name "Net-(U5-RT)") (class "Default")
      (node (ref "R29") (pin "2") (pinfunction "2_2") (pintype "passive"))
      (node (ref "U5") (pin "15") (pinfunction "RT_15") (pintype "bidirectional"))
    )
    (net (code "39") (name "Net-(U5-TR{slash}SS)") (class "Default")
      (node (ref "C32") (pin "2") (pinfunction "2_2") (pintype "passive"))
      (node (ref "U5") (pin "16") (pinfunction "TR/SS_16") (pintype "bidirectional"))
    )
    (net (code "40") (name "Net-(U7-INTERRUPT)") (class "Default")
      (node (ref "R4") (pin "2") (pinfunction "2_2") (pintype "passive"))
      (node (ref "U7") (pin "P$37") (pinfunction "INTERRUPT_P$37") (pintype "bidirectional"))
    )
    (net (code "41") (name "Net-(U7-LDO)") (class "Default")
      (node (ref "C34") (pin "1") (pinfunction "1_1") (pintype "passive"))
      (node (ref "U7") (pin "P$43") (pinfunction "LDO_P$43") (pintype "bidirectional"))
    )
    (net (code "42") (name "Net-(U7-Q1)") (class "Default")
      (node (ref "C25") (pin "1") (pinfunction "1_1") (pintype "passive"))
      (node (ref "U7") (pin "P$48") (pinfunction "Q1_P$48") (pintype "bidirectional"))
    )
    (net (code "43") (name "Net-(U7-Q2)") (class "Default")
      (node (ref "C25") (pin "2") (pinfunction "2_2") (pintype "passive"))
      (node (ref "U7") (pin "P$47") (pinfunction "Q2_P$47") (pintype "bidirectional"))
    )
    (net (code "44") (name "Net-(U7-Q3)") (class "Default")
      (node (ref "C26") (pin "1") (pinfunction "1_1") (pintype "passive"))
      (node (ref "U7") (pin "P$46") (pinfunction "Q3_P$46") (pintype "bidirectional"))
    )
    (net (code "45") (name "Net-(U7-VREFOUT)") (class "Default")
      (node (ref "C20") (pin "1") (pinfunction "1_1") (pintype "passive"))
      (node (ref "U7") (pin "P$13") (pinfunction "VREFOUT_P$13") (pintype "bidirectional"))
      (node (ref "U7") (pin "P$14") (pinfunction "VREFP_P$14") (pintype "bidirectional"))
    )
    (net (code "46") (name "Net-(U7-VREF_BYP)") (class "Default")
      (node (ref "C19") (pin "1") (pinfunction "1_1") (pintype "passive"))
      (node (ref "U7") (pin "P$11") (pinfunction "VREF_BYP_P$11") (pintype "bidirectional"))
    )
    (net (code "47") (name "P2") (class "Default")
      (node (ref "U1") (pin "43") (pinfunction "P2_43") (pintype "bidirectional"))
    )
    (net (code "48") (name "P3") (class "Default")
      (node (ref "U1") (pin "44") (pinfunction "P3_44") (pintype "bidirectional"))
    )
    (net (code "49") (name "P4") (class "Default")
      (node (ref "U1") (pin "1") (pinfunction "P4_1") (pintype "bidirectional"))
    )
    (net (code "50") (name "P5") (class "Default")
      (node (ref "U1") (pin "2") (pinfunction "P5_2") (pintype "bidirectional"))
    )
    (net (code "51") (name "P6") (class "Default")
      (node (ref "U1") (pin "3") (pinfunction "P6_3") (pintype "bidirectional"))
    )
    (net (code "52") (name "P13") (class "Default")
      (node (ref "U1") (pin "14") (pinfunction "P13_14") (pintype "bidirectional"))
    )
    (net (code "53") (name "P14") (class "Default")
      (node (ref "U1") (pin "15") (pinfunction "P14_15") (pintype "bidirectional"))
    )
    (net (code "54") (name "P15") (class "Default")
      (node (ref "U1") (pin "16") (pinfunction "P15_16") (pintype "bidirectional"))
    )
    (net (code "55") (name "P16") (class "Default")
      (node (ref "U1") (pin "19") (pinfunction "P16_19") (pintype "bidirectional"))
    )
    (net (code "56") (name "P17") (class "Default")
      (node (ref "U1") (pin "20") (pinfunction "P17_20") (pintype "bidirectional"))
    )
    (net (code "57") (name "P18") (class "Default")
      (node (ref "U1") (pin "21") (pinfunction "P18_21") (pintype "bidirectional"))
    )
    (net (code "58") (name "P19") (class "Default")
      (node (ref "U1") (pin "22") (pinfunction "P19_22") (pintype "bidirectional"))
    )
    (net (code "59") (name "P20") (class "Default")
      (node (ref "U1") (pin "23") (pinfunction "P20_23") (pintype "bidirectional"))
    )
    (net (code "60") (name "P21") (class "Default")
      (node (ref "U1") (pin "24") (pinfunction "P21_24") (pintype "bidirectional"))
    )
    (net (code "61") (name "P22") (class "Default")
      (node (ref "U1") (pin "25") (pinfunction "P22_25") (pintype "bidirectional"))
    )
    (net (code "62") (name "P23") (class "Default")
      (node (ref "U1") (pin "26") (pinfunction "P23_26") (pintype "bidirectional"))
    )
    (net (code "63") (name "P24") (class "Default")
      (node (ref "U1") (pin "31") (pinfunction "P24_31") (pintype "bidirectional"))
    )
    (net (code "64") (name "P25") (class "Default")
      (node (ref "U1") (pin "32") (pinfunction "P25_32") (pintype "bidirectional"))
    )
    (net (code "65") (name "P26") (class "Default")
      (node (ref "U1") (pin "33") (pinfunction "P26_33") (pintype "bidirectional"))
    )
    (net (code "66") (name "P27") (class "Default")
      (node (ref "U1") (pin "34") (pinfunction "P27_34") (pintype "bidirectional"))
    )
    (net (code "67") (name "PROP_RES") (class "Default")
      (node (ref "C5") (pin "2") (pinfunction "2_2") (pintype "passive"))
      (node (ref "R1") (pin "1") (pinfunction "1_1") (pintype "passive"))
      (node (ref "U1") (pin "7") (pinfunction "RES'_7") (pintype "bidirectional"))
    )
    (net (code "68") (name "RX_PROP") (class "Default")
      (node (ref "FTDI_CABLE") (pin "4") (pinfunction "4_4") (pintype "passive"))
      (node (ref "TAG_CONNECT") (pin "P$4") (pinfunction "PIN4_P$4") (pintype "bidirectional"))
      (node (ref "U1") (pin "38") (pinfunction "P31_38") (pintype "bidirectional"))
    )
    (net (code "69") (name "SCL") (class "Default")
      (node (ref "U1") (pin "35") (pinfunction "P28_35") (pintype "bidirectional"))
      (node (ref "U2") (pin "6") (pinfunction "SCL_6") (pintype "bidirectional"))
    )
    (net (code "70") (name "SDA") (class "Default")
      (node (ref "U1") (pin "36") (pinfunction "P29_36") (pintype "bidirectional"))
      (node (ref "U2") (pin "5") (pinfunction "SDA_5") (pintype "bidirectional"))
    )
    (net (code "71") (name "SPI_LEVEL_SHIFTER_OE") (class "Default")
      (node (ref "R3") (pin "2") (pinfunction "2_2") (pintype "passive"))
      (node (ref "U1") (pin "12") (pinfunction "P11_12") (pintype "bidirectional"))
      (node (ref "U8") (pin "8") (pinfunction "OE_8") (pintype "bidirectional"))
    )
    (net (code "72") (name "TX_PROP") (class "Default")
      (node (ref "FTDI_CABLE") (pin "5") (pinfunction "5_5") (pintype "passive"))
      (node (ref "TAG_CONNECT") (pin "P$3") (pinfunction "PIN3_P$3") (pintype "bidirectional"))
      (node (ref "U1") (pin "37") (pinfunction "P30_37") (pintype "bidirectional"))
    )
    (net (code "73") (name "VIN") (class "Default")
      (node (ref "D1") (pin "C") (pinfunction "CATHODE_C") (pintype "bidirectional"))
      (node (ref "J2") (pin "1A") (pinfunction "PIN1_1A") (pintype "bidirectional"))
      (node (ref "J2") (pin "1B") (pinfunction "PIN1_1B") (pintype "bidirectional"))
      (node (ref "U3") (pin "9") (pinfunction "SOURCE_9") (pintype "bidirectional"))
      (node (ref "U6") (pin "3") (pinfunction "SOURCE_3") (pintype "bidirectional"))
    )
    (net (code "74") (name "unconnected-(FTDI_CABLE-Pad2)") (class "Default")
      (node (ref "FTDI_CABLE") (pin "2") (pinfunction "2_2") (pintype "passive"))
    )
    (net (code "75") (name "unconnected-(FTDI_CABLE-Pad3)") (class "Default")
      (node (ref "FTDI_CABLE") (pin "3") (pinfunction "3_3") (pintype "passive"))
    )
    (net (code "76") (name "unconnected-(J1-3-PadP$3)") (class "Default")
      (node (ref "J1") (pin "P$3") (pinfunction "3_P$3") (pintype "bidirectional"))
    )
    (net (code "77") (name "unconnected-(J1-4-PadP$4)") (class "Default")
      (node (ref "J1") (pin "P$4") (pinfunction "4_P$4") (pintype "bidirectional"))
    )
    (net (code "78") (name "unconnected-(J1-5-PadP$5)") (class "Default")
      (node (ref "J1") (pin "P$5") (pinfunction "5_P$5") (pintype "bidirectional"))
    )
    (net (code "79") (name "unconnected-(J1-6-PadP$6)") (class "Default")
      (node (ref "J1") (pin "P$6") (pinfunction "6_P$6") (pintype "bidirectional"))
    )
    (net (code "80") (name "unconnected-(J1-7-PadP$7)") (class "Default")
      (node (ref "J1") (pin "P$7") (pinfunction "7_P$7") (pintype "bidirectional"))
    )
    (net (code "81") (name "unconnected-(J1-8-PadP$8)") (class "Default")
      (node (ref "J1") (pin "P$8") (pinfunction "8_P$8") (pintype "bidirectional"))
    )
    (net (code "82") (name "unconnected-(J1-14-PadP$14)") (class "Default")
      (node (ref "J1") (pin "P$14") (pinfunction "14_P$14") (pintype "bidirectional"))
    )
    (net (code "83") (name "unconnected-(TAG_CONNECT-PIN1-PadP$1)") (class "Default")
      (node (ref "TAG_CONNECT") (pin "P$1") (pinfunction "PIN1_P$1") (pintype "bidirectional"))
    )
    (net (code "84") (name "unconnected-(TAG_CONNECT-PIN2-PadP$2)") (class "Default")
      (node (ref "TAG_CONNECT") (pin "P$2") (pinfunction "PIN2_P$2") (pintype "bidirectional"))
    )
    (net (code "85") (name "unconnected-(U2-A0-Pad1)") (class "Default")
      (node (ref "U2") (pin "1") (pinfunction "A0_1") (pintype "bidirectional"))
    )
    (net (code "86") (name "unconnected-(U3-EN{slash}UVLO-Pad1)") (class "Default")
      (node (ref "U3") (pin "1") (pinfunction "EN/UVLO_1") (pintype "bidirectional"))
    )
    (net (code "87") (name "unconnected-(U3-PG-Pad3)") (class "Default")
      (node (ref "U3") (pin "3") (pinfunction "PG_3") (pintype "bidirectional"))
    )
    (net (code "88") (name "unconnected-(U4-PG-Pad19)") (class "Default")
      (node (ref "U4") (pin "19") (pinfunction "PG_19") (pintype "bidirectional"))
    )
    (net (code "89") (name "unconnected-(U4-SYNC{slash}MODE-Pad17)") (class "Default")
      (node (ref "U4") (pin "17") (pinfunction "SYNC/MODE_17") (pintype "bidirectional"))
    )
    (net (code "90") (name "unconnected-(U5-PG-Pad19)") (class "Default")
      (node (ref "U5") (pin "19") (pinfunction "PG_19") (pintype "bidirectional"))
    )
    (net (code "91") (name "unconnected-(U5-SYNC{slash}MODE-Pad17)") (class "Default")
      (node (ref "U5") (pin "17") (pinfunction "SYNC/MODE_17") (pintype "bidirectional"))
    )
    (net (code "92") (name "unconnected-(U7-CH1-PadP$16)") (class "Default")
      (node (ref "U7") (pin "P$16") (pinfunction "CH1_P$16") (pintype "bidirectional"))
    )
    (net (code "93") (name "unconnected-(U7-CH2-PadP$17)") (class "Default")
      (node (ref "U7") (pin "P$17") (pinfunction "CH2_P$17") (pintype "bidirectional"))
    )
    (net (code "94") (name "unconnected-(U7-CH3-PadP$18)") (class "Default")
      (node (ref "U7") (pin "P$18") (pinfunction "CH3_P$18") (pintype "bidirectional"))
    )
    (net (code "95") (name "unconnected-(U7-CH4-PadP$19)") (class "Default")
      (node (ref "U7") (pin "P$19") (pinfunction "CH4_P$19") (pintype "bidirectional"))
    )
    (net (code "96") (name "unconnected-(U7-CH5-PadP$20)") (class "Default")
      (node (ref "U7") (pin "P$20") (pinfunction "CH5_P$20") (pintype "bidirectional"))
    )
    (net (code "97") (name "unconnected-(U7-CH6-PadP$21)") (class "Default")
      (node (ref "U7") (pin "P$21") (pinfunction "CH6_P$21") (pintype "bidirectional"))
    )
    (net (code "98") (name "unconnected-(U7-CH7-PadP$22)") (class "Default")
      (node (ref "U7") (pin "P$22") (pinfunction "CH7_P$22") (pintype "bidirectional"))
    )
    (net (code "99") (name "unconnected-(U7-CH8-PadP$23)") (class "Default")
      (node (ref "U7") (pin "P$23") (pinfunction "CH8_P$23") (pintype "bidirectional"))
    )
    (net (code "100") (name "unconnected-(U7-CH9-PadP$24)") (class "Default")
      (node (ref "U7") (pin "P$24") (pinfunction "CH9_P$24") (pintype "bidirectional"))
    )
    (net (code "101") (name "unconnected-(U7-CH10-PadP$25)") (class "Default")
      (node (ref "U7") (pin "P$25") (pinfunction "CH10_P$25") (pintype "bidirectional"))
    )
    (net (code "102") (name "unconnected-(U7-COM-PadP$36)") (class "Default")
      (node (ref "U7") (pin "P$36") (pinfunction "COM_P$36") (pintype "bidirectional"))
    )
  )
)
